# Voltages.net
KiCad netlist of a schematic drawn in Altium Designer
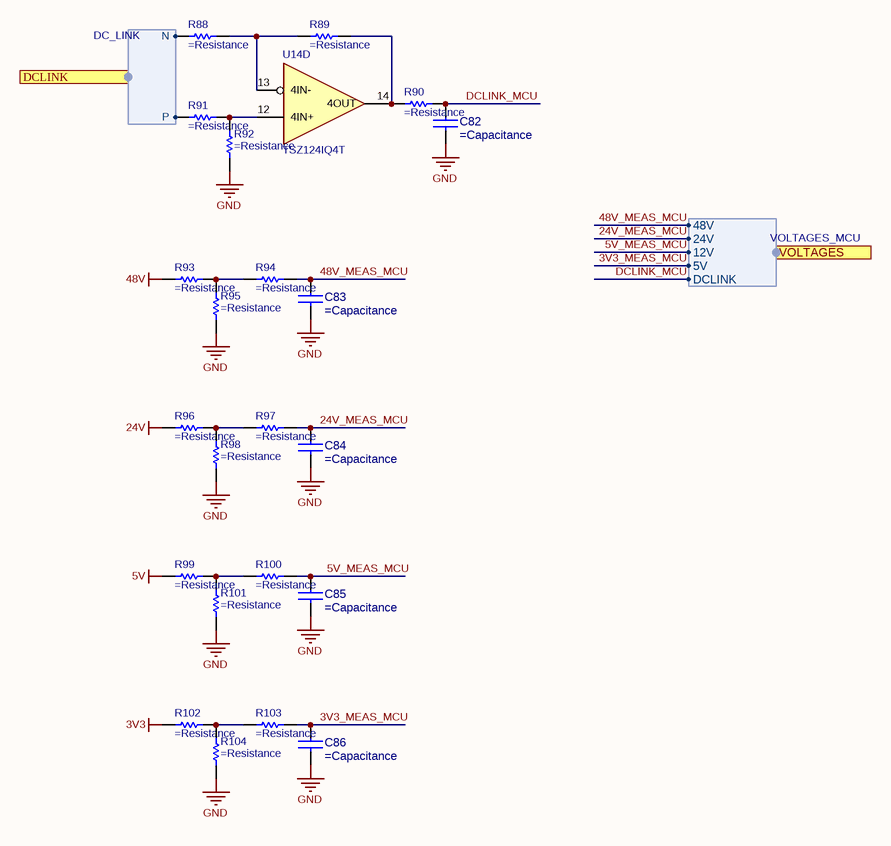
[diagram p0: Voltages.SchDoc]

(export (version "E")
  (design (tool "Eeschema 10.0.6"))
  (components
    (comp (ref "C82")
      (value "~")
      (footprint "C0402")
      (description "Multilayer Ceramic Capacitors MLCC - SMD/SMT 25V 6800pF X7R 0402 10% AEC-Q200")
      (fields
        (field (name "MANUFACTURER") "KEMET")
        (field (name "MANUFACTURER PART NUMBER") "C0402C682K3RACAUTO")
      )
      (libsource (lib "Capacitors") (part "CAP0402-6.8nF-25V"))
    )
    (comp (ref "C83")
      (value "~")
      (footprint "C0402")
      (description "Multilayer Ceramic Capacitors MLCC - SMD/SMT 25V 6800pF X7R 0402 10% AEC-Q200")
      (fields
        (field (name "MANUFACTURER") "KEMET")
        (field (name "MANUFACTURER PART NUMBER") "C0402C682K3RACAUTO")
      )
      (libsource (lib "Capacitors") (part "CAP0402-6.8nF-25V"))
    )
    (comp (ref "C84")
      (value "~")
      (footprint "C0402")
      (description "Multilayer Ceramic Capacitors MLCC - SMD/SMT 25V 6800pF X7R 0402 10% AEC-Q200")
      (fields
        (field (name "MANUFACTURER") "KEMET")
        (field (name "MANUFACTURER PART NUMBER") "C0402C682K3RACAUTO")
      )
      (libsource (lib "Capacitors") (part "CAP0402-6.8nF-25V"))
    )
    (comp (ref "C85")
      (value "~")
      (footprint "C0402")
      (description "Multilayer Ceramic Capacitors MLCC - SMD/SMT 25V 6800pF X7R 0402 10% AEC-Q200")
      (fields
        (field (name "MANUFACTURER") "KEMET")
        (field (name "MANUFACTURER PART NUMBER") "C0402C682K3RACAUTO")
      )
      (libsource (lib "Capacitors") (part "CAP0402-6.8nF-25V"))
    )
    (comp (ref "C86")
      (value "~")
      (footprint "C0402")
      (description "Multilayer Ceramic Capacitors MLCC - SMD/SMT 25V 6800pF X7R 0402 10% AEC-Q200")
      (fields
        (field (name "MANUFACTURER") "KEMET")
        (field (name "MANUFACTURER PART NUMBER") "C0402C682K3RACAUTO")
      )
      (libsource (lib "Capacitors") (part "CAP0402-6.8nF-25V"))
    )
    (comp (ref "R88")
      (value "~")
      (footprint "R0402")
      (description "Res Thick Film 0402 1K Ohm 1% 0.063W(1/16W) ±50ppm/C Pad SMD Automotive T/R")
      (fields
        (field (name "MANUFACTURER") "Vishay")
        (field (name "MANUFACTURER PART NUMBER") "CRCW04021K00FHEDP")
      )
      (libsource (lib "Resistors") (part "RES0402-1k-1%"))
    )
    (comp (ref "R89")
      (value "~")
      (footprint "R0402")
      (description "Res Thick Film 0402 2K Ohm 1% 1/16W 100ppm/C Molded SMD SMD Paper T/R")
      (fields
        (field (name "MANUFACTURER") "Vishay")
        (field (name "MANUFACTURER PART NUMBER") "CRCW04022K00FKEE")
      )
      (libsource (lib "Resistors") (part "RES0402-2k-1%"))
    )
    (comp (ref "R90")
      (value "~")
      (footprint "R0402")
      (description "Res Thick Film 0402 1K Ohm 1% 0.063W(1/16W) ±50ppm/C Pad SMD Automotive T/R")
      (fields
        (field (name "MANUFACTURER") "Vishay")
        (field (name "MANUFACTURER PART NUMBER") "CRCW04021K00FHEDP")
      )
      (libsource (lib "Resistors") (part "RES0402-1k-1%"))
    )
    (comp (ref "R91")
      (value "~")
      (footprint "R0402")
      (description "Res Thick Film 0402 1K Ohm 1% 0.063W(1/16W) ±50ppm/C Pad SMD Automotive T/R")
      (fields
        (field (name "MANUFACTURER") "Vishay")
        (field (name "MANUFACTURER PART NUMBER") "CRCW04021K00FHEDP")
      )
      (libsource (lib "Resistors") (part "RES0402-1k-1%"))
    )
    (comp (ref "R92")
      (value "~")
      (footprint "R0402")
      (description "Res Thick Film 0402 2K Ohm 1% 1/16W 100ppm/C Molded SMD SMD Paper T/R")
      (fields
        (field (name "MANUFACTURER") "Vishay")
        (field (name "MANUFACTURER PART NUMBER") "CRCW04022K00FKEE")
      )
      (libsource (lib "Resistors") (part "RES0402-2k-1%"))
    )
    (comp (ref "R93")
      (value "~")
      (footprint "R0402")
      (description "Res Thick Film 0402 47K Ohm 1% 0.063W(1/16W) ±100ppm/C Pad SMD T/R")
      (fields
        (field (name "MANUFACTURER") "Vishay")
        (field (name "MANUFACTURER PART NUMBER") "CRCW040247K0FKEDC")
      )
      (libsource (lib "Resistors") (part "RES0402-47k-1%"))
    )
    (comp (ref "R94")
      (value "~")
      (footprint "R0402")
      (description "Res Thick Film 0402 10K Ohm 1% 0.063W(1/16W) ±100ppm/C Pad SMD T/R Automotive AEC-Q200")
      (fields
        (field (name "MANUFACTURER") "Vishay")
        (field (name "MANUFACTURER PART NUMBER") "CRCW040210K0FKEE")
      )
      (libsource (lib "Resistors") (part "RES0402-10k-1%"))
    )
    (comp (ref "R95")
      (value "~")
      (footprint "R0402")
      (description "Res Thick Film 0402 2K Ohm 1% 1/16W 100ppm/C Molded SMD SMD Paper T/R")
      (fields
        (field (name "MANUFACTURER") "Vishay")
        (field (name "MANUFACTURER PART NUMBER") "CRCW04022K00FKEE")
      )
      (libsource (lib "Resistors") (part "RES0402-2k-1%"))
    )
    (comp (ref "R96")
      (value "~")
      (footprint "R0402")
      (description "Res Thick Film 0402 20K Ohm 1% 0.063W(1/16W) ±100ppm/C Pad SMD T/R")
      (fields
        (field (name "MANUFACTURER") "Vishay")
        (field (name "MANUFACTURER PART NUMBER") "CRCW040220K0FKEDC")
      )
      (libsource (lib "Resistors") (part "RES0402-20k-1%"))
    )
    (comp (ref "R97")
      (value "~")
      (footprint "R0402")
      (description "Res Thick Film 0402 10K Ohm 1% 0.063W(1/16W) ±100ppm/C Pad SMD T/R Automotive AEC-Q200")
      (fields
        (field (name "MANUFACTURER") "Vishay")
        (field (name "MANUFACTURER PART NUMBER") "CRCW040210K0FKEE")
      )
      (libsource (lib "Resistors") (part "RES0402-10k-1%"))
    )
    (comp (ref "R98")
      (value "~")
      (footprint "R0402")
      (description "Res Thick Film 0402 2K Ohm 1% 1/16W 100ppm/C Molded SMD SMD Paper T/R")
      (fields
        (field (name "MANUFACTURER") "Vishay")
        (field (name "MANUFACTURER PART NUMBER") "CRCW04022K00FKEE")
      )
      (libsource (lib "Resistors") (part "RES0402-2k-1%"))
    )
    (comp (ref "R99")
      (value "~")
      (footprint "R0402")
      (description "Res Thick Film 0402 20K Ohm 1% 0.063W(1/16W) ±100ppm/C Pad SMD T/R")
      (fields
        (field (name "MANUFACTURER") "Vishay")
        (field (name "MANUFACTURER PART NUMBER") "CRCW040220K0FKEDC")
      )
      (libsource (lib "Resistors") (part "RES0402-20k-1%"))
    )
    (comp (ref "R100")
      (value "~")
      (footprint "R0402")
      (description "Res Thick Film 0402 10K Ohm 1% 0.063W(1/16W) ±100ppm/C Pad SMD T/R Automotive AEC-Q200")
      (fields
        (field (name "MANUFACTURER") "Vishay")
        (field (name "MANUFACTURER PART NUMBER") "CRCW040210K0FKEE")
      )
      (libsource (lib "Resistors") (part "RES0402-10k-1%"))
    )
    (comp (ref "R101")
      (value "~")
      (footprint "R0402")
      (description "0402 30K Ohms 1% High Power Thick Film Surface Mount Chip Resistor")
      (fields
        (field (name "MANUFACTURER") "Vishay")
        (field (name "MANUFACTURER PART NUMBER") "CRCW040230K0FKEDHP")
      )
      (libsource (lib "Resistors") (part "RES0402-30k-1%"))
    )
    (comp (ref "R102")
      (value "~")
      (footprint "R0402")
      (description "Res Thick Film 0402 10K Ohm 1% 0.063W(1/16W) ±100ppm/C Pad SMD T/R Automotive AEC-Q200")
      (fields
        (field (name "MANUFACTURER") "Vishay")
        (field (name "MANUFACTURER PART NUMBER") "CRCW040210K0FKEE")
      )
      (libsource (lib "Resistors") (part "RES0402-10k-1%"))
    )
    (comp (ref "R103")
      (value "~")
      (footprint "R0402")
      (description "Res Thick Film 0402 10K Ohm 1% 0.063W(1/16W) ±100ppm/C Pad SMD T/R Automotive AEC-Q200")
      (fields
        (field (name "MANUFACTURER") "Vishay")
        (field (name "MANUFACTURER PART NUMBER") "CRCW040210K0FKEE")
      )
      (libsource (lib "Resistors") (part "RES0402-10k-1%"))
    )
    (comp (ref "R104")
      (value "~")
      (footprint "R0402")
      (description "Res Thick Film 0402 10K Ohm 1% 0.063W(1/16W) ±100ppm/C Pad SMD T/R Automotive AEC-Q200")
      (fields
        (field (name "MANUFACTURER") "Vishay")
        (field (name "MANUFACTURER PART NUMBER") "CRCW040210K0FKEE")
      )
      (libsource (lib "Resistors") (part "RES0402-10k-1%"))
    )
    (comp (ref "U14")
      (value "TSZ124IQ4T")
      (footprint "VQFN16")
      (description "TSZ124 Series 5.5V 400 kHz Rail to Rail SMT Operational Amplifier - TSSOP-14")
      (fields (field (name "MANUFACTURER") "STMicroelectronics"))
      (libsource (lib "IC") (part "TSZ124IQ4T"))
    )
  )
  (nets
    (net (code "3") (name "/3V3_MEAS_MCU") (class "Default")
      (node (ref "C86") (pin "1") (pinfunction "1_1") (pintype "passive"))
      (node (ref "R103") (pin "2") (pinfunction "2_2") (pintype "passive"))
    )
    (net (code "4") (name "/5V_MEAS_MCU") (class "Default")
      (node (ref "C85") (pin "1") (pinfunction "1_1") (pintype "passive"))
      (node (ref "R100") (pin "2") (pinfunction "2_2") (pintype "passive"))
    )
    (net (code "5") (name "/24V_MEAS_MCU") (class "Default")
      (node (ref "C84") (pin "1") (pinfunction "1_1") (pintype "passive"))
      (node (ref "R97") (pin "2") (pinfunction "2_2") (pintype "passive"))
    )
    (net (code "6") (name "/48V_MEAS_MCU") (class "Default")
      (node (ref "C83") (pin "1") (pinfunction "1_1") (pintype "passive"))
      (node (ref "R94") (pin "2") (pinfunction "2_2") (pintype "passive"))
    )
    (net (code "7") (name "/DCLINK_MCU") (class "Default")
      (node (ref "C82") (pin "1") (pinfunction "1_1") (pintype "passive"))
      (node (ref "R90") (pin "2") (pinfunction "2_2") (pintype "passive"))
    )
    (net (code "8") (name "/N") (class "Default")
      (node (ref "R88") (pin "1") (pinfunction "1_1") (pintype "passive"))
    )
    (net (code "9") (name "/P") (class "Default")
      (node (ref "R91") (pin "1") (pinfunction "1_1") (pintype "passive"))
    )
    (net (code "12") (name "3V3") (class "Default")
      (node (ref "R102") (pin "1") (pinfunction "1_1") (pintype "passive"))
    )
    (net (code "13") (name "5V") (class "Default")
      (node (ref "R99") (pin "1") (pinfunction "1_1") (pintype "passive"))
    )
    (net (code "14") (name "24V") (class "Default")
      (node (ref "R96") (pin "1") (pinfunction "1_1") (pintype "passive"))
    )
    (net (code "15") (name "48V") (class "Default")
      (node (ref "R93") (pin "1") (pinfunction "1_1") (pintype "passive"))
    )
    (net (code "16") (name "GND") (class "Default")
      (node (ref "C82") (pin "2") (pinfunction "2_2") (pintype "passive"))
      (node (ref "C83") (pin "2") (pinfunction "2_2") (pintype "passive"))
      (node (ref "C84") (pin "2") (pinfunction "2_2") (pintype "passive"))
      (node (ref "C85") (pin "2") (pinfunction "2_2") (pintype "passive"))
      (node (ref "C86") (pin "2") (pinfunction "2_2") (pintype "passive"))
      (node (ref "R101") (pin "1") (pinfunction "1_1") (pintype "passive"))
      (node (ref "R104") (pin "1") (pinfunction "1_1") (pintype "passive"))
      (node (ref "R92") (pin "1") (pinfunction "1_1") (pintype "passive"))
      (node (ref "R95") (pin "1") (pinfunction "1_1") (pintype "passive"))
      (node (ref "R98") (pin "1") (pinfunction "1_1") (pintype "passive"))
    )
    (net (code "17") (name "Net-(R93-Pad2)") (class "Default")
      (node (ref "R93") (pin "2") (pinfunction "2_2") (pintype "passive"))
      (node (ref "R94") (pin "1") (pinfunction "1_1") (pintype "passive"))
      (node (ref "R95") (pin "2") (pinfunction "2_2") (pintype "passive"))
    )
    (net (code "18") (name "Net-(R96-Pad2)") (class "Default")
      (node (ref "R96") (pin "2") (pinfunction "2_2") (pintype "passive"))
      (node (ref "R97") (pin "1") (pinfunction "1_1") (pintype "passive"))
      (node (ref "R98") (pin "2") (pinfunction "2_2") (pintype "passive"))
    )
    (net (code "19") (name "Net-(R100-Pad1)") (class "Default")
      (node (ref "R100") (pin "1") (pinfunction "1_1") (pintype "passive"))
      (node (ref "R101") (pin "2") (pinfunction "2_2") (pintype "passive"))
      (node (ref "R99") (pin "2") (pinfunction "2_2") (pintype "passive"))
    )
    (net (code "20") (name "Net-(R102-Pad2)") (class "Default")
      (node (ref "R102") (pin "2") (pinfunction "2_2") (pintype "passive"))
      (node (ref "R103") (pin "1") (pinfunction "1_1") (pintype "passive"))
      (node (ref "R104") (pin "2") (pinfunction "2_2") (pintype "passive"))
    )
    (net (code "21") (name "Net-(U14D-4IN+)") (class "Default")
      (node (ref "R91") (pin "2") (pinfunction "2_2") (pintype "passive"))
      (node (ref "R92") (pin "2") (pinfunction "2_2") (pintype "passive"))
      (node (ref "U14") (pin "12") (pinfunction "4IN+_12") (pintype "passive"))
    )
    (net (code "22") (name "Net-(U14D-4IN-)") (class "Default")
      (node (ref "R88") (pin "2") (pinfunction "2_2") (pintype "passive"))
      (node (ref "R89") (pin "1") (pinfunction "1_1") (pintype "passive"))
      (node (ref "U14") (pin "13") (pinfunction "4IN-_13") (pintype "passive"))
    )
    (net (code "23") (name "Net-(U14D-4OUT)") (class "Default")
      (node (ref "R89") (pin "2") (pinfunction "2_2") (pintype "passive"))
      (node (ref "R90") (pin "1") (pinfunction "1_1") (pintype "passive"))
      (node (ref "U14") (pin "14") (pinfunction "4OUT_14") (pintype "passive"))
    )
  )
)
